# project_hail_fally.net
KiCad netlist of a schematic drawn in EasyEDA Pro
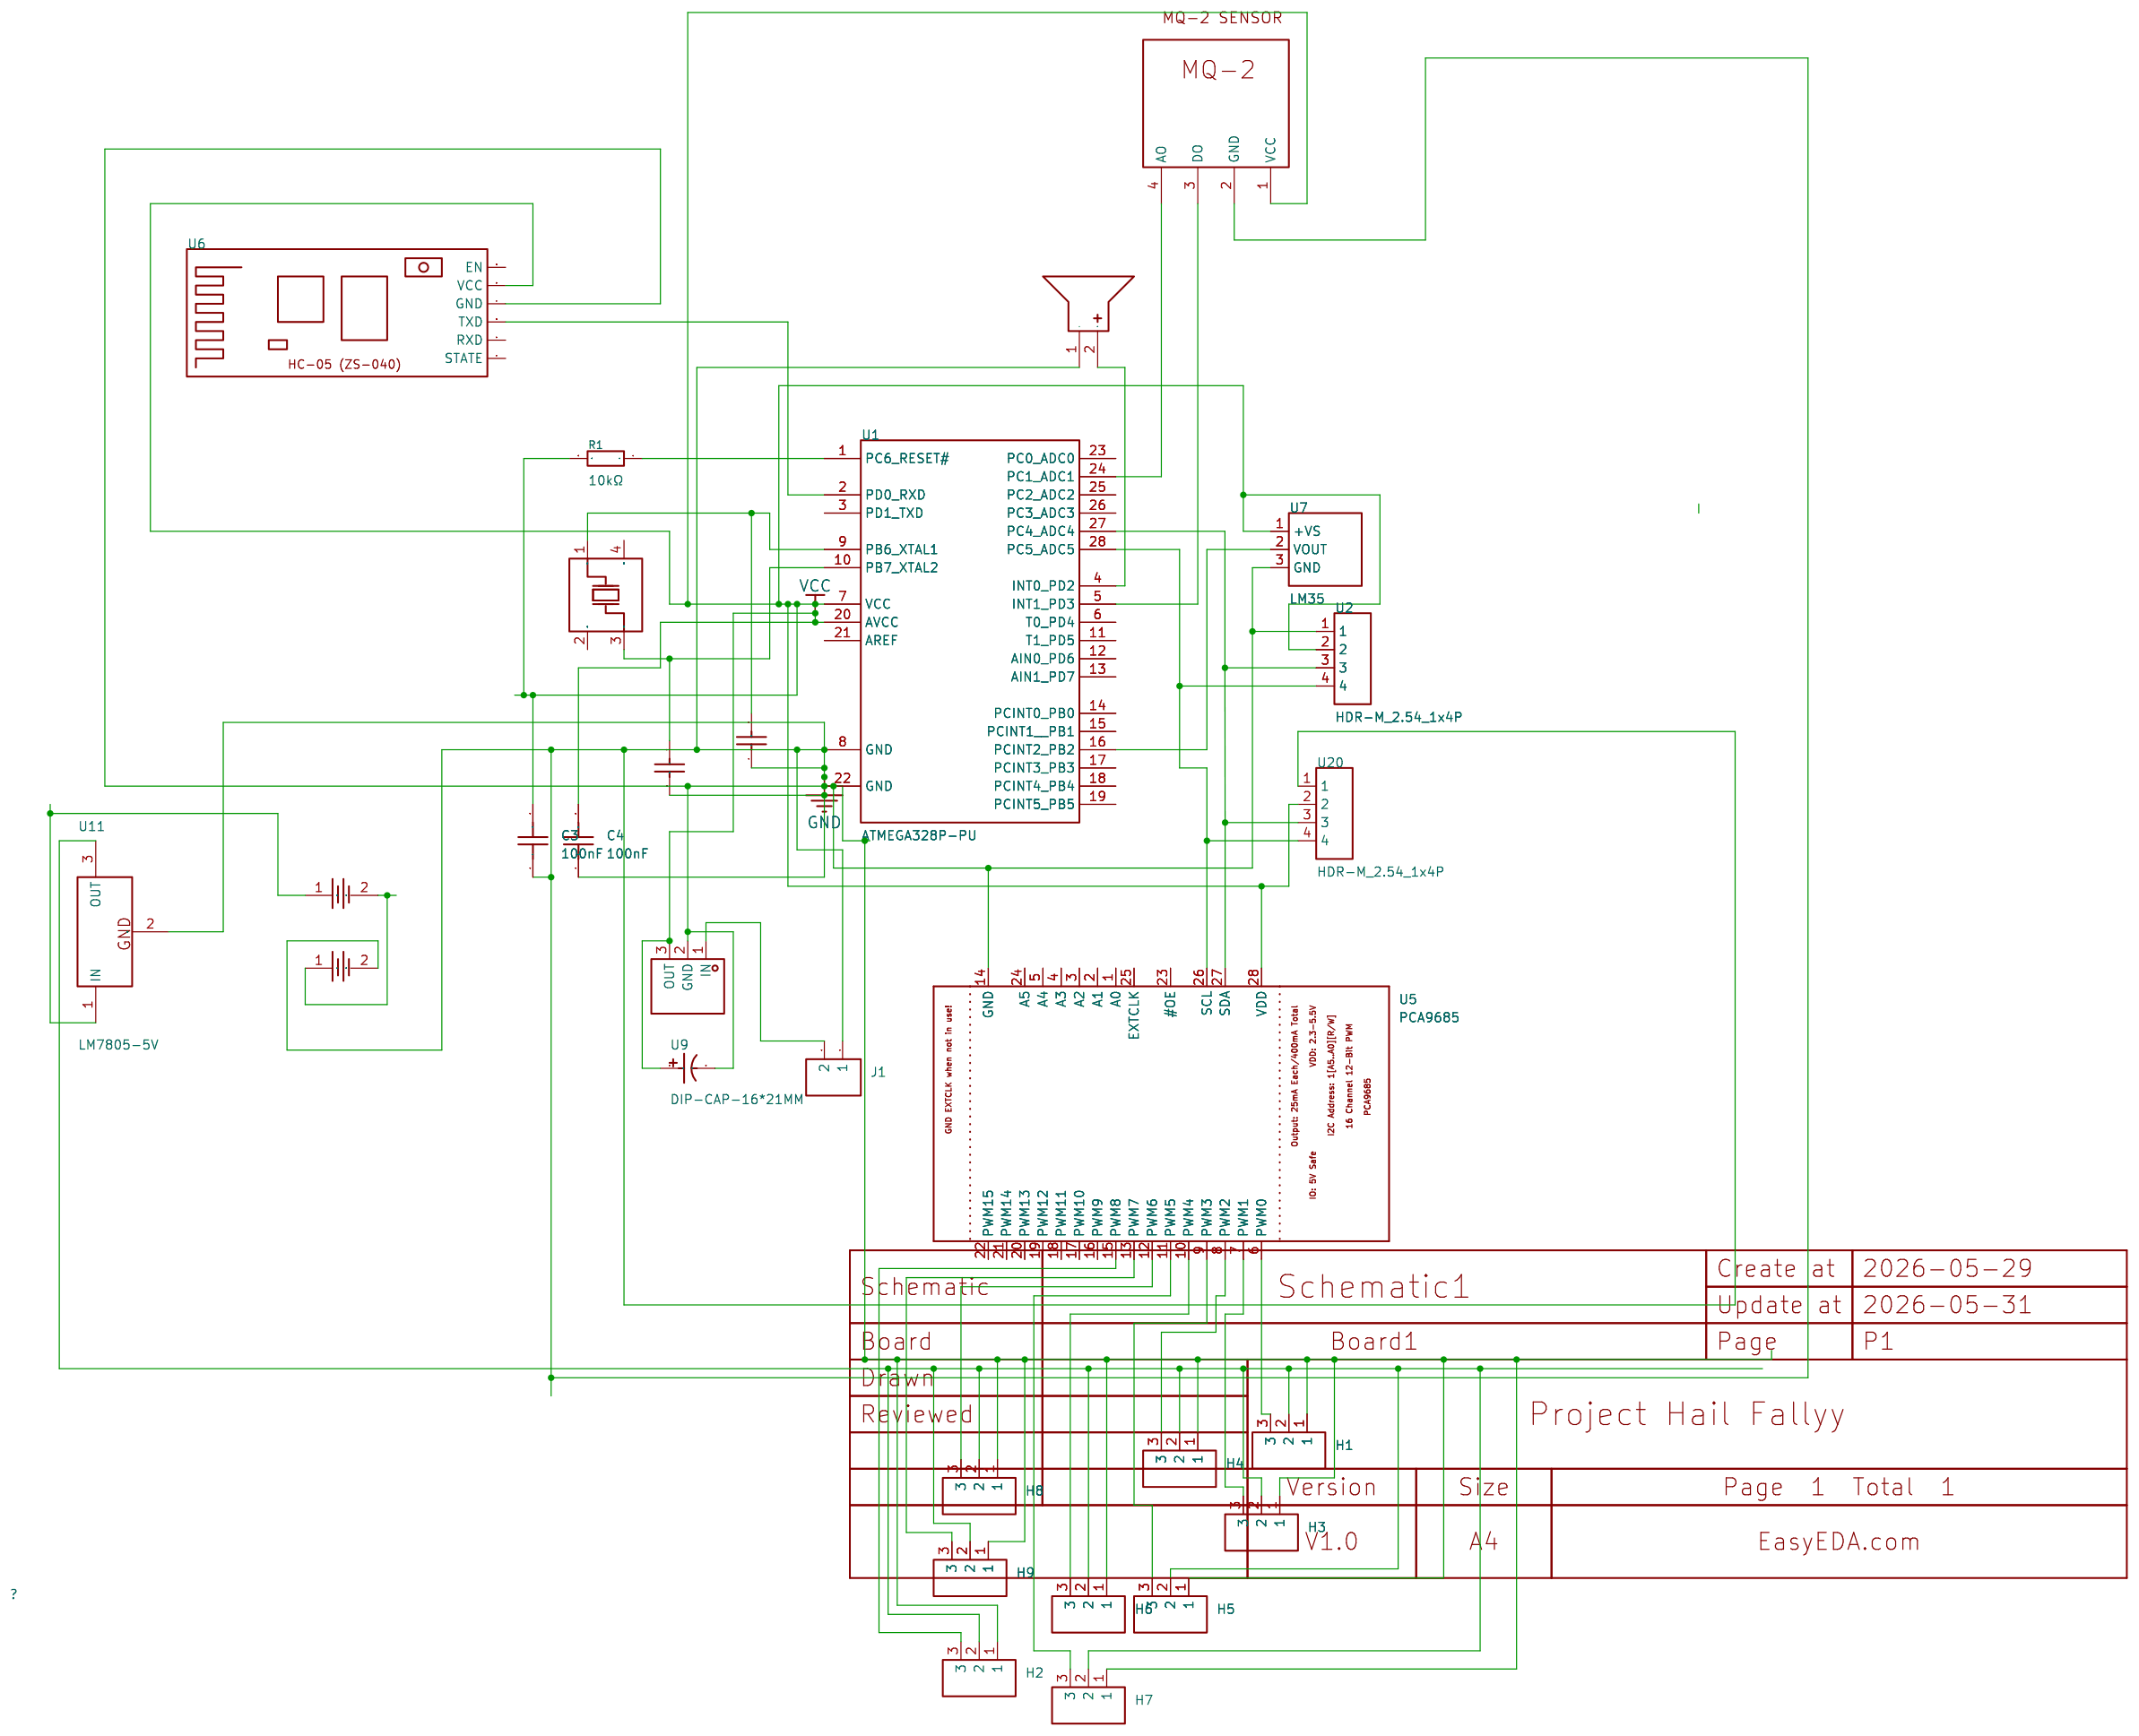
[diagram p0: schematic sheet]

(export (version "E")
  (design (tool "Eeschema 10.0.6"))
  (components
    (comp (ref "BT1")
      (value "BH-18650-A5BJ001")
      (footprint "easyedapro:BAT-TH_18650-A5BJ001")
      (fields (field (name "Manufacturer") "MYOUNG(美阳)"))
      (libsource (lib "easyedapro") (part "BH-18650-A5BJ001"))
    )
    (comp (ref "BT2")
      (value "BH-18650-A5BJ001")
      (footprint "easyedapro:BAT-TH_18650-A5BJ001")
      (fields (field (name "Manufacturer") "MYOUNG(美阳)"))
      (libsource (lib "easyedapro") (part "BH-18650-A5BJ001"))
    )
    (comp (ref "BUZZER1")
      (value "buzzer")
      (footprint "easyedapro:BUZ-TH_BD12.0-P6.00-D0.9-RD")
      (libsource (lib "easyedapro") (part "BUZZER"))
    )
    (comp (ref "C1")
      (value "22pF")
      (footprint "easyedapro:C0805")
      (fields
        (field (name "Manufacturer Part") "CL21C220JBANNNC")
        (field (name "Manufacturer") "SAMSUNG(三星)")
      )
      (libsource (lib "easyedapro") (part "CL21C220JBANNNC"))
    )
    (comp (ref "C2")
      (value "22pF")
      (footprint "easyedapro:C0805")
      (fields
        (field (name "Manufacturer Part") "CL21C220JBANNNC")
        (field (name "Manufacturer") "SAMSUNG(三星)")
      )
      (libsource (lib "easyedapro") (part "CL21C220JBANNNC"))
    )
    (comp (ref "C3")
      (value "100nF")
      (footprint "easyedapro:C0402")
      (fields
        (field (name "Manufacturer Part") "CL05B104KB54PNC")
        (field (name "Manufacturer") "SAMSUNG(三星)")
      )
      (libsource (lib "easyedapro") (part "CL05B104KB54PNC"))
    )
    (comp (ref "C4")
      (value "100nF")
      (footprint "easyedapro:C0402")
      (fields
        (field (name "Manufacturer Part") "CL05B104KB54PNC")
        (field (name "Manufacturer") "SAMSUNG(三星)")
      )
      (libsource (lib "easyedapro") (part "CL05B104KB54PNC"))
    )
    (comp (ref "H1")
      (value "~")
      (footprint "easyedapro:HDR-TH_3P-P2.54-V-M")
      (libsource (lib "easyedapro") (part "PZ254V-11-03P_C2937625"))
    )
    (comp (ref "H2")
      (value "~")
      (footprint "easyedapro:HDR-TH_3P-P2.54-V-M")
      (libsource (lib "easyedapro") (part "PZ254V-11-03P_C2937625"))
    )
    (comp (ref "H3")
      (value "~")
      (footprint "easyedapro:HDR-TH_3P-P2.54-V-M")
      (libsource (lib "easyedapro") (part "PZ254V-11-03P_C2937625"))
    )
    (comp (ref "H4")
      (value "~")
      (footprint "easyedapro:HDR-TH_3P-P2.54-V-M")
      (libsource (lib "easyedapro") (part "PZ254V-11-03P_C2937625"))
    )
    (comp (ref "H5")
      (value "~")
      (footprint "easyedapro:HDR-TH_3P-P2.54-V-M")
      (libsource (lib "easyedapro") (part "PZ254V-11-03P_C2937625"))
    )
    (comp (ref "H6")
      (value "~")
      (footprint "easyedapro:HDR-TH_3P-P2.54-V-M")
      (libsource (lib "easyedapro") (part "PZ254V-11-03P_C2937625"))
    )
    (comp (ref "H7")
      (value "~")
      (footprint "easyedapro:HDR-TH_3P-P2.54-V-M")
      (libsource (lib "easyedapro") (part "PZ254V-11-03P_C2937625"))
    )
    (comp (ref "H8")
      (value "~")
      (footprint "easyedapro:HDR-TH_3P-P2.54-V-M")
      (libsource (lib "easyedapro") (part "PZ254V-11-03P_C2937625"))
    )
    (comp (ref "H9")
      (value "~")
      (footprint "easyedapro:HDR-TH_3P-P2.54-V-M")
      (libsource (lib "easyedapro") (part "PZ254V-11-03P_C2937625"))
    )
    (comp (ref "J1")
      (value "Bettery Connector")
      (footprint "easyedapro:HDR-M-2.54_1X2")
      (libsource (lib "easyedapro") (part "Bettery Connector"))
    )
    (comp (ref "R1")
      (value "10kΩ")
      (footprint "easyedapro:R1206")
      (fields
        (field (name "Manufacturer Part") "1206W4F1002T5E")
        (field (name "Manufacturer") "UNI-ROYAL(厚声)")
      )
      (libsource (lib "easyedapro") (part "1206W4F1002T5E"))
    )
    (comp (ref "S1")
      (value "Sensor_MQ-2_module_vertical_AIH")
      (footprint "easyedapro:SENSOR_MQ-2_MODULE_VERTICAL_AIH")
      (libsource (lib "easyedapro") (part "MQ-2"))
    )
    (comp (ref "U1")
      (value "ATMEGA328P-PU")
      (footprint "easyedapro:DIP-28_L34.6-W7.3-P2.54-LS10.2-BL")
      (fields (field (name "Manufacturer") "MICROCHIP(美国微芯)"))
      (libsource (lib "easyedapro") (part "ATMEGA328P-PU"))
    )
    (comp (ref "U2")
      (value "HDR-M_2.54_1x4P")
      (footprint "easyedapro:HDR-TH_HDR-M_2.54_1X4P")
      (libsource (lib "easyedapro") (part "HDR-M_2.54_1X4P"))
    )
    (comp (ref "U3")
      (value "LM7805")
      (footprint "easyedapro:TO-220-3_L10.0-W4.5-P2.54-L")
      (fields (field (name "Manufacturer") "TF(拓锋)"))
      (libsource (lib "easyedapro") (part "LM7805"))
    )
    (comp (ref "U5")
      (value "PCA9685")
      (footprint "easyedapro:TSSOP28")
      (libsource (lib "easyedapro") (part "PCA9685"))
    )
    (comp (ref "U6")
      (value "HC05-Bluetooth-Module_AK")
      (footprint "easyedapro:hc05-bluetooth-module_ak")
      (libsource (lib "easyedapro") (part "HC05-Bluetooth-Module_AK"))
    )
    (comp (ref "U7")
      (value "LM35")
      (footprint "easyedapro:TO-92-3_L4.8-W3.7-P1.27-L")
      (fields (field (name "Manufacturer") "Silicore(芯谷)"))
      (libsource (lib "easyedapro") (part "LM35"))
    )
    (comp (ref "U9")
      (value "470uF")
      (footprint "easyedapro:CAP-TH_BD13.0-P5.00-D0.6-FD")
      (fields (field (name "Manufacturer Part") "DIP-CAP-16*21MM"))
      (libsource (lib "easyedapro") (part "DIP-CAP-16*21MM"))
    )
    (comp (ref "U11")
      (value "LM7805-5V")
      (footprint "easyedapro:TO-252-2_L6.6-W6.1-P4.58-LS9.9-TL")
      (libsource (lib "easyedapro") (part "LM7805-5V_C9900008050"))
    )
    (comp (ref "U20")
      (value "HDR-M_2.54_1x4P")
      (footprint "easyedapro:HDR-TH_HDR-M_2.54_1X4P")
      (libsource (lib "easyedapro") (part "HDR-M_2.54_1X4P"))
    )
    (comp (ref "X1")
      (value "16MHz")
      (footprint "easyedapro:CRYSTAL-SMD_4P-L3.2-W2.5-BL")
      (fields (field (name "Manufacturer Part") "X322516MLB4SI") (field (name "Manufacturer") "YXC(扬兴晶振)"))
      (libsource (lib "easyedapro") (part "X322516MLB4SI"))
    )
  )
  (nets
    (net (code "1") (name "GND") (class "Default")
      (node (ref "BT2") (pin "2") (pinfunction "2_2") (pintype "input"))
      (node (ref "BUZZER1") (pin "1") (pinfunction "-_1") (pintype "input"))
      (node (ref "C1") (pin "1") (pinfunction "1_1") (pintype "input"))
      (node (ref "C2") (pin "2") (pinfunction "2_2") (pintype "input"))
      (node (ref "C3") (pin "1") (pinfunction "1_1") (pintype "input"))
      (node (ref "C4") (pin "1") (pinfunction "1_1") (pintype "input"))
      (node (ref "H1") (pin "1") (pinfunction "1_1") (pintype "unspecified"))
      (node (ref "H2") (pin "1") (pinfunction "1_1") (pintype "unspecified"))
      (node (ref "H3") (pin "1") (pinfunction "1_1") (pintype "unspecified"))
      (node (ref "H4") (pin "1") (pinfunction "1_1") (pintype "unspecified"))
      (node (ref "H5") (pin "1") (pinfunction "1_1") (pintype "unspecified"))
      (node (ref "H6") (pin "1") (pinfunction "1_1") (pintype "unspecified"))
      (node (ref "H7") (pin "1") (pinfunction "1_1") (pintype "unspecified"))
      (node (ref "H8") (pin "1") (pinfunction "1_1") (pintype "unspecified"))
      (node (ref "H9") (pin "1") (pinfunction "1_1") (pintype "unspecified"))
      (node (ref "J1") (pin "1") (pinfunction "1_1") (pintype "unspecified"))
      (node (ref "S1") (pin "2") (pinfunction "GND_2") (pintype "unspecified"))
      (node (ref "U1") (pin "22") (pinfunction "GND_22") (pintype "unspecified"))
      (node (ref "U1") (pin "8") (pinfunction "GND_8") (pintype "unspecified"))
      (node (ref "U11") (pin "2") (pinfunction "GND_2") (pintype "input"))
      (node (ref "U2") (pin "1") (pinfunction "1_1") (pintype "unspecified"))
      (node (ref "U20") (pin "1") (pinfunction "1_1") (pintype "unspecified"))
      (node (ref "U3") (pin "2") (pinfunction "GND_2") (pintype "input"))
      (node (ref "U5") (pin "14") (pinfunction "GND_14") (pintype "unspecified"))
      (node (ref "U6") (pin "4") (pinfunction "GND_4") (pintype "input"))
      (node (ref "U7") (pin "3") (pinfunction "GND_3") (pintype "unspecified"))
      (node (ref "U9") (pin "2") (pinfunction "2_2") (pintype "input"))
    )
    (net (code "2") (name "Net-(BT1-Pad2)") (class "Default")
      (node (ref "BT1") (pin "2") (pinfunction "2_2") (pintype "input"))
      (node (ref "BT2") (pin "1") (pinfunction "1_1") (pintype "input"))
    )
    (net (code "3") (name "Net-(BUZZER1-+)") (class "Default")
      (node (ref "BUZZER1") (pin "2") (pinfunction "+_2") (pintype "input"))
      (node (ref "U1") (pin "4") (pinfunction "INT0_PD2_4") (pintype "bidirectional"))
    )
    (net (code "4") (name "Net-(S1-AO)") (class "Default")
      (node (ref "S1") (pin "4") (pinfunction "AO_4") (pintype "unspecified"))
      (node (ref "U1") (pin "24") (pinfunction "PC1_ADC1_24") (pintype "bidirectional"))
    )
    (net (code "5") (name "Net-(S1-DO)") (class "Default")
      (node (ref "S1") (pin "3") (pinfunction "DO_3") (pintype "unspecified"))
      (node (ref "U1") (pin "5") (pinfunction "INT1_PD3_5") (pintype "bidirectional"))
    )
    (net (code "6") (name "Net-(U1-PB6_XTAL1)") (class "Default")
      (node (ref "C1") (pin "2") (pinfunction "2_2") (pintype "input"))
      (node (ref "U1") (pin "9") (pinfunction "PB6_XTAL1_9") (pintype "bidirectional"))
      (node (ref "X1") (pin "1") (pinfunction "OSC1_1") (pintype "unspecified"))
    )
    (net (code "7") (name "Net-(U1-PB7_XTAL2)") (class "Default")
      (node (ref "C2") (pin "1") (pinfunction "1_1") (pintype "input"))
      (node (ref "U1") (pin "10") (pinfunction "PB7_XTAL2_10") (pintype "bidirectional"))
      (node (ref "X1") (pin "3") (pinfunction "OSC2_3") (pintype "unspecified"))
    )
    (net (code "8") (name "Net-(U1-PC4_ADC4)") (class "Default")
      (node (ref "U1") (pin "27") (pinfunction "PC4_ADC4_27") (pintype "bidirectional"))
      (node (ref "U2") (pin "3") (pinfunction "3_3") (pintype "unspecified"))
      (node (ref "U20") (pin "3") (pinfunction "3_3") (pintype "unspecified"))
      (node (ref "U5") (pin "27") (pinfunction "SDA_27") (pintype "bidirectional"))
    )
    (net (code "9") (name "Net-(U1-PC5_ADC5)") (class "Default")
      (node (ref "U1") (pin "28") (pinfunction "PC5_ADC5_28") (pintype "bidirectional"))
      (node (ref "U2") (pin "4") (pinfunction "4_4") (pintype "unspecified"))
      (node (ref "U20") (pin "4") (pinfunction "4_4") (pintype "unspecified"))
      (node (ref "U5") (pin "26") (pinfunction "SCL_26") (pintype "bidirectional"))
    )
    (net (code "10") (name "Net-(U1-PC6_RESET#)") (class "Default")
      (node (ref "R1") (pin "1") (pinfunction "1_1") (pintype "input"))
      (node (ref "U1") (pin "1") (pinfunction "PC6_RESET#_1") (pintype "bidirectional"))
    )
    (net (code "11") (name "Net-(U1-PCINT2_PB2)") (class "Default")
      (node (ref "U1") (pin "16") (pinfunction "PCINT2_PB2_16") (pintype "bidirectional"))
      (node (ref "U7") (pin "2") (pinfunction "VOUT_2") (pintype "unspecified"))
    )
    (net (code "12") (name "Net-(U1-PD0_RXD)") (class "Default")
      (node (ref "U1") (pin "2") (pinfunction "PD0_RXD_2") (pintype "bidirectional"))
      (node (ref "U6") (pin "3") (pinfunction "TXD_3") (pintype "input"))
    )
    (net (code "13") (name "Net-(U3-IN)") (class "Default")
      (node (ref "J1") (pin "2") (pinfunction "2_2") (pintype "unspecified"))
      (node (ref "U3") (pin "1") (pinfunction "IN_1") (pintype "input"))
    )
    (net (code "14") (name "Net-(U5-PWM0)") (class "Default")
      (node (ref "H1") (pin "3") (pinfunction "3_3") (pintype "unspecified"))
      (node (ref "U5") (pin "6") (pinfunction "PWM0_6") (pintype "output"))
    )
    (net (code "15") (name "Net-(U5-PWM1)") (class "Default")
      (node (ref "H3") (pin "3") (pinfunction "3_3") (pintype "unspecified"))
      (node (ref "U5") (pin "7") (pinfunction "PWM1_7") (pintype "output"))
    )
    (net (code "16") (name "Net-(U5-PWM2)") (class "Default")
      (node (ref "H4") (pin "3") (pinfunction "3_3") (pintype "unspecified"))
      (node (ref "U5") (pin "8") (pinfunction "PWM2_8") (pintype "output"))
    )
    (net (code "17") (name "Net-(U5-PWM3)") (class "Default")
      (node (ref "H5") (pin "3") (pinfunction "3_3") (pintype "unspecified"))
      (node (ref "U5") (pin "9") (pinfunction "PWM3_9") (pintype "output"))
    )
    (net (code "18") (name "Net-(U5-PWM4)") (class "Default")
      (node (ref "H6") (pin "3") (pinfunction "3_3") (pintype "unspecified"))
      (node (ref "U5") (pin "10") (pinfunction "PWM4_10") (pintype "output"))
    )
    (net (code "19") (name "Net-(U5-PWM5)") (class "Default")
      (node (ref "H7") (pin "3") (pinfunction "3_3") (pintype "unspecified"))
      (node (ref "U5") (pin "11") (pinfunction "PWM5_11") (pintype "output"))
    )
    (net (code "20") (name "Net-(U5-PWM6)") (class "Default")
      (node (ref "H8") (pin "3") (pinfunction "3_3") (pintype "unspecified"))
      (node (ref "U5") (pin "12") (pinfunction "PWM6_12") (pintype "output"))
    )
    (net (code "21") (name "Net-(U5-PWM7)") (class "Default")
      (node (ref "H9") (pin "3") (pinfunction "3_3") (pintype "unspecified"))
      (node (ref "U5") (pin "13") (pinfunction "PWM7_13") (pintype "output"))
    )
    (net (code "22") (name "Net-(U5-PWM8)") (class "Default")
      (node (ref "H2") (pin "3") (pinfunction "3_3") (pintype "unspecified"))
      (node (ref "U5") (pin "15") (pinfunction "PWM8_15") (pintype "output"))
    )
    (net (code "23") (name "Net-(U11-IN)") (class "Default")
      (node (ref "BT1") (pin "1") (pinfunction "1_1") (pintype "input"))
      (node (ref "U11") (pin "1") (pinfunction "IN_1") (pintype "input"))
    )
    (net (code "24") (name "Net-(U11-OUT)") (class "Default")
      (node (ref "H1") (pin "2") (pinfunction "2_2") (pintype "unspecified"))
      (node (ref "H2") (pin "2") (pinfunction "2_2") (pintype "unspecified"))
      (node (ref "H3") (pin "2") (pinfunction "2_2") (pintype "unspecified"))
      (node (ref "H4") (pin "2") (pinfunction "2_2") (pintype "unspecified"))
      (node (ref "H5") (pin "2") (pinfunction "2_2") (pintype "unspecified"))
      (node (ref "H6") (pin "2") (pinfunction "2_2") (pintype "unspecified"))
      (node (ref "H7") (pin "2") (pinfunction "2_2") (pintype "unspecified"))
      (node (ref "H8") (pin "2") (pinfunction "2_2") (pintype "unspecified"))
      (node (ref "H9") (pin "2") (pinfunction "2_2") (pintype "unspecified"))
      (node (ref "U11") (pin "3") (pinfunction "OUT_3") (pintype "input"))
    )
    (net (code "25") (name "VCC") (class "Default")
      (node (ref "C3") (pin "2") (pinfunction "2_2") (pintype "input"))
      (node (ref "C4") (pin "2") (pinfunction "2_2") (pintype "input"))
      (node (ref "R1") (pin "2") (pinfunction "2_2") (pintype "input"))
      (node (ref "S1") (pin "1") (pinfunction "VCC_1") (pintype "unspecified"))
      (node (ref "U1") (pin "20") (pinfunction "AVCC_20") (pintype "unspecified"))
      (node (ref "U1") (pin "7") (pinfunction "VCC_7") (pintype "unspecified"))
      (node (ref "U2") (pin "2") (pinfunction "2_2") (pintype "unspecified"))
      (node (ref "U20") (pin "2") (pinfunction "2_2") (pintype "unspecified"))
      (node (ref "U3") (pin "3") (pinfunction "OUT_3") (pintype "input"))
      (node (ref "U5") (pin "28") (pinfunction "VDD_28") (pintype "unspecified"))
      (node (ref "U6") (pin "5") (pinfunction "VCC_5") (pintype "output"))
      (node (ref "U7") (pin "1") (pinfunction "+VS_1") (pintype "unspecified"))
      (node (ref "U9") (pin "1") (pinfunction "1_1") (pintype "input"))
    )
    (net (code "26") (name "unconnected-(U1-AIN0_PD6-Pad12)") (class "Default")
      (node (ref "U1") (pin "12") (pinfunction "AIN0_PD6_12") (pintype "bidirectional"))
    )
    (net (code "27") (name "unconnected-(U1-AIN1_PD7-Pad13)") (class "Default")
      (node (ref "U1") (pin "13") (pinfunction "AIN1_PD7_13") (pintype "bidirectional"))
    )
    (net (code "28") (name "unconnected-(U1-AREF-Pad21)") (class "Default")
      (node (ref "U1") (pin "21") (pinfunction "AREF_21") (pintype "unspecified"))
    )
    (net (code "29") (name "unconnected-(U1-PC0_ADC0-Pad23)") (class "Default")
      (node (ref "U1") (pin "23") (pinfunction "PC0_ADC0_23") (pintype "bidirectional"))
    )
    (net (code "30") (name "unconnected-(U1-PC2_ADC2-Pad25)") (class "Default")
      (node (ref "U1") (pin "25") (pinfunction "PC2_ADC2_25") (pintype "bidirectional"))
    )
    (net (code "31") (name "unconnected-(U1-PC3_ADC3-Pad26)") (class "Default")
      (node (ref "U1") (pin "26") (pinfunction "PC3_ADC3_26") (pintype "bidirectional"))
    )
    (net (code "32") (name "unconnected-(U1-PCINT0_PB0-Pad14)") (class "Default")
      (node (ref "U1") (pin "14") (pinfunction "PCINT0_PB0_14") (pintype "bidirectional"))
    )
    (net (code "33") (name "unconnected-(U1-PCINT1__PB1-Pad15)") (class "Default")
      (node (ref "U1") (pin "15") (pinfunction "PCINT1__PB1_15") (pintype "bidirectional"))
    )
    (net (code "34") (name "unconnected-(U1-PCINT3_PB3-Pad17)") (class "Default")
      (node (ref "U1") (pin "17") (pinfunction "PCINT3_PB3_17") (pintype "bidirectional"))
    )
    (net (code "35") (name "unconnected-(U1-PCINT4_PB4-Pad18)") (class "Default")
      (node (ref "U1") (pin "18") (pinfunction "PCINT4_PB4_18") (pintype "bidirectional"))
    )
    (net (code "36") (name "unconnected-(U1-PCINT5_PB5-Pad19)") (class "Default")
      (node (ref "U1") (pin "19") (pinfunction "PCINT5_PB5_19") (pintype "bidirectional"))
    )
    (net (code "37") (name "unconnected-(U1-PD1_TXD-Pad3)") (class "Default")
      (node (ref "U1") (pin "3") (pinfunction "PD1_TXD_3") (pintype "bidirectional"))
    )
    (net (code "38") (name "unconnected-(U1-T0_PD4-Pad6)") (class "Default")
      (node (ref "U1") (pin "6") (pinfunction "T0_PD4_6") (pintype "bidirectional"))
    )
    (net (code "39") (name "unconnected-(U1-T1_PD5-Pad11)") (class "Default")
      (node (ref "U1") (pin "11") (pinfunction "T1_PD5_11") (pintype "bidirectional"))
    )
    (net (code "40") (name "unconnected-(U5-#OE-Pad23)") (class "Default")
      (node (ref "U5") (pin "23") (pinfunction "#OE_23") (pintype "input"))
    )
    (net (code "41") (name "unconnected-(U5-A0-Pad1)") (class "Default")
      (node (ref "U5") (pin "1") (pinfunction "A0_1") (pintype "bidirectional"))
    )
    (net (code "42") (name "unconnected-(U5-A1-Pad2)") (class "Default")
      (node (ref "U5") (pin "2") (pinfunction "A1_2") (pintype "bidirectional"))
    )
    (net (code "43") (name "unconnected-(U5-A2-Pad3)") (class "Default")
      (node (ref "U5") (pin "3") (pinfunction "A2_3") (pintype "bidirectional"))
    )
    (net (code "44") (name "unconnected-(U5-A3-Pad4)") (class "Default")
      (node (ref "U5") (pin "4") (pinfunction "A3_4") (pintype "bidirectional"))
    )
    (net (code "45") (name "unconnected-(U5-A4-Pad5)") (class "Default")
      (node (ref "U5") (pin "5") (pinfunction "A4_5") (pintype "bidirectional"))
    )
    (net (code "46") (name "unconnected-(U5-A5-Pad24)") (class "Default")
      (node (ref "U5") (pin "24") (pinfunction "A5_24") (pintype "bidirectional"))
    )
    (net (code "47") (name "unconnected-(U5-EXTCLK-Pad25)") (class "Default")
      (node (ref "U5") (pin "25") (pinfunction "EXTCLK_25") (pintype "input"))
    )
    (net (code "48") (name "unconnected-(U5-PWM9-Pad16)") (class "Default")
      (node (ref "U5") (pin "16") (pinfunction "PWM9_16") (pintype "output"))
    )
    (net (code "49") (name "unconnected-(U5-PWM10-Pad17)") (class "Default")
      (node (ref "U5") (pin "17") (pinfunction "PWM10_17") (pintype "output"))
    )
    (net (code "50") (name "unconnected-(U5-PWM11-Pad18)") (class "Default")
      (node (ref "U5") (pin "18") (pinfunction "PWM11_18") (pintype "output"))
    )
    (net (code "51") (name "unconnected-(U5-PWM12-Pad19)") (class "Default")
      (node (ref "U5") (pin "19") (pinfunction "PWM12_19") (pintype "output"))
    )
    (net (code "52") (name "unconnected-(U5-PWM13-Pad20)") (class "Default")
      (node (ref "U5") (pin "20") (pinfunction "PWM13_20") (pintype "output"))
    )
    (net (code "53") (name "unconnected-(U5-PWM14-Pad21)") (class "Default")
      (node (ref "U5") (pin "21") (pinfunction "PWM14_21") (pintype "output"))
    )
    (net (code "54") (name "unconnected-(U5-PWM15-Pad22)") (class "Default")
      (node (ref "U5") (pin "22") (pinfunction "PWM15_22") (pintype "output"))
    )
    (net (code "55") (name "unconnected-(U6-EN-Pad6)") (class "Default")
      (node (ref "U6") (pin "6") (pinfunction "EN_6") (pintype "bidirectional"))
    )
    (net (code "56") (name "unconnected-(U6-RXD-Pad2)") (class "Default")
      (node (ref "U6") (pin "2") (pinfunction "RXD_2") (pintype "input"))
    )
    (net (code "57") (name "unconnected-(U6-STATE-Pad1)") (class "Default")
      (node (ref "U6") (pin "1") (pinfunction "STATE_1") (pintype "input"))
    )
    (net (code "58") (name "unconnected-(X1-GND-Pad2)") (class "Default")
      (node (ref "X1") (pin "2") (pinfunction "GND_2") (pintype "unspecified"))
    )
    (net (code "59") (name "unconnected-(X1-GND-Pad4)") (class "Default")
      (node (ref "X1") (pin "4") (pinfunction "GND_4") (pintype "unspecified"))
    )
  )
)
